# DELPHI.net
KiCad netlist of a schematic drawn in Altium Designer
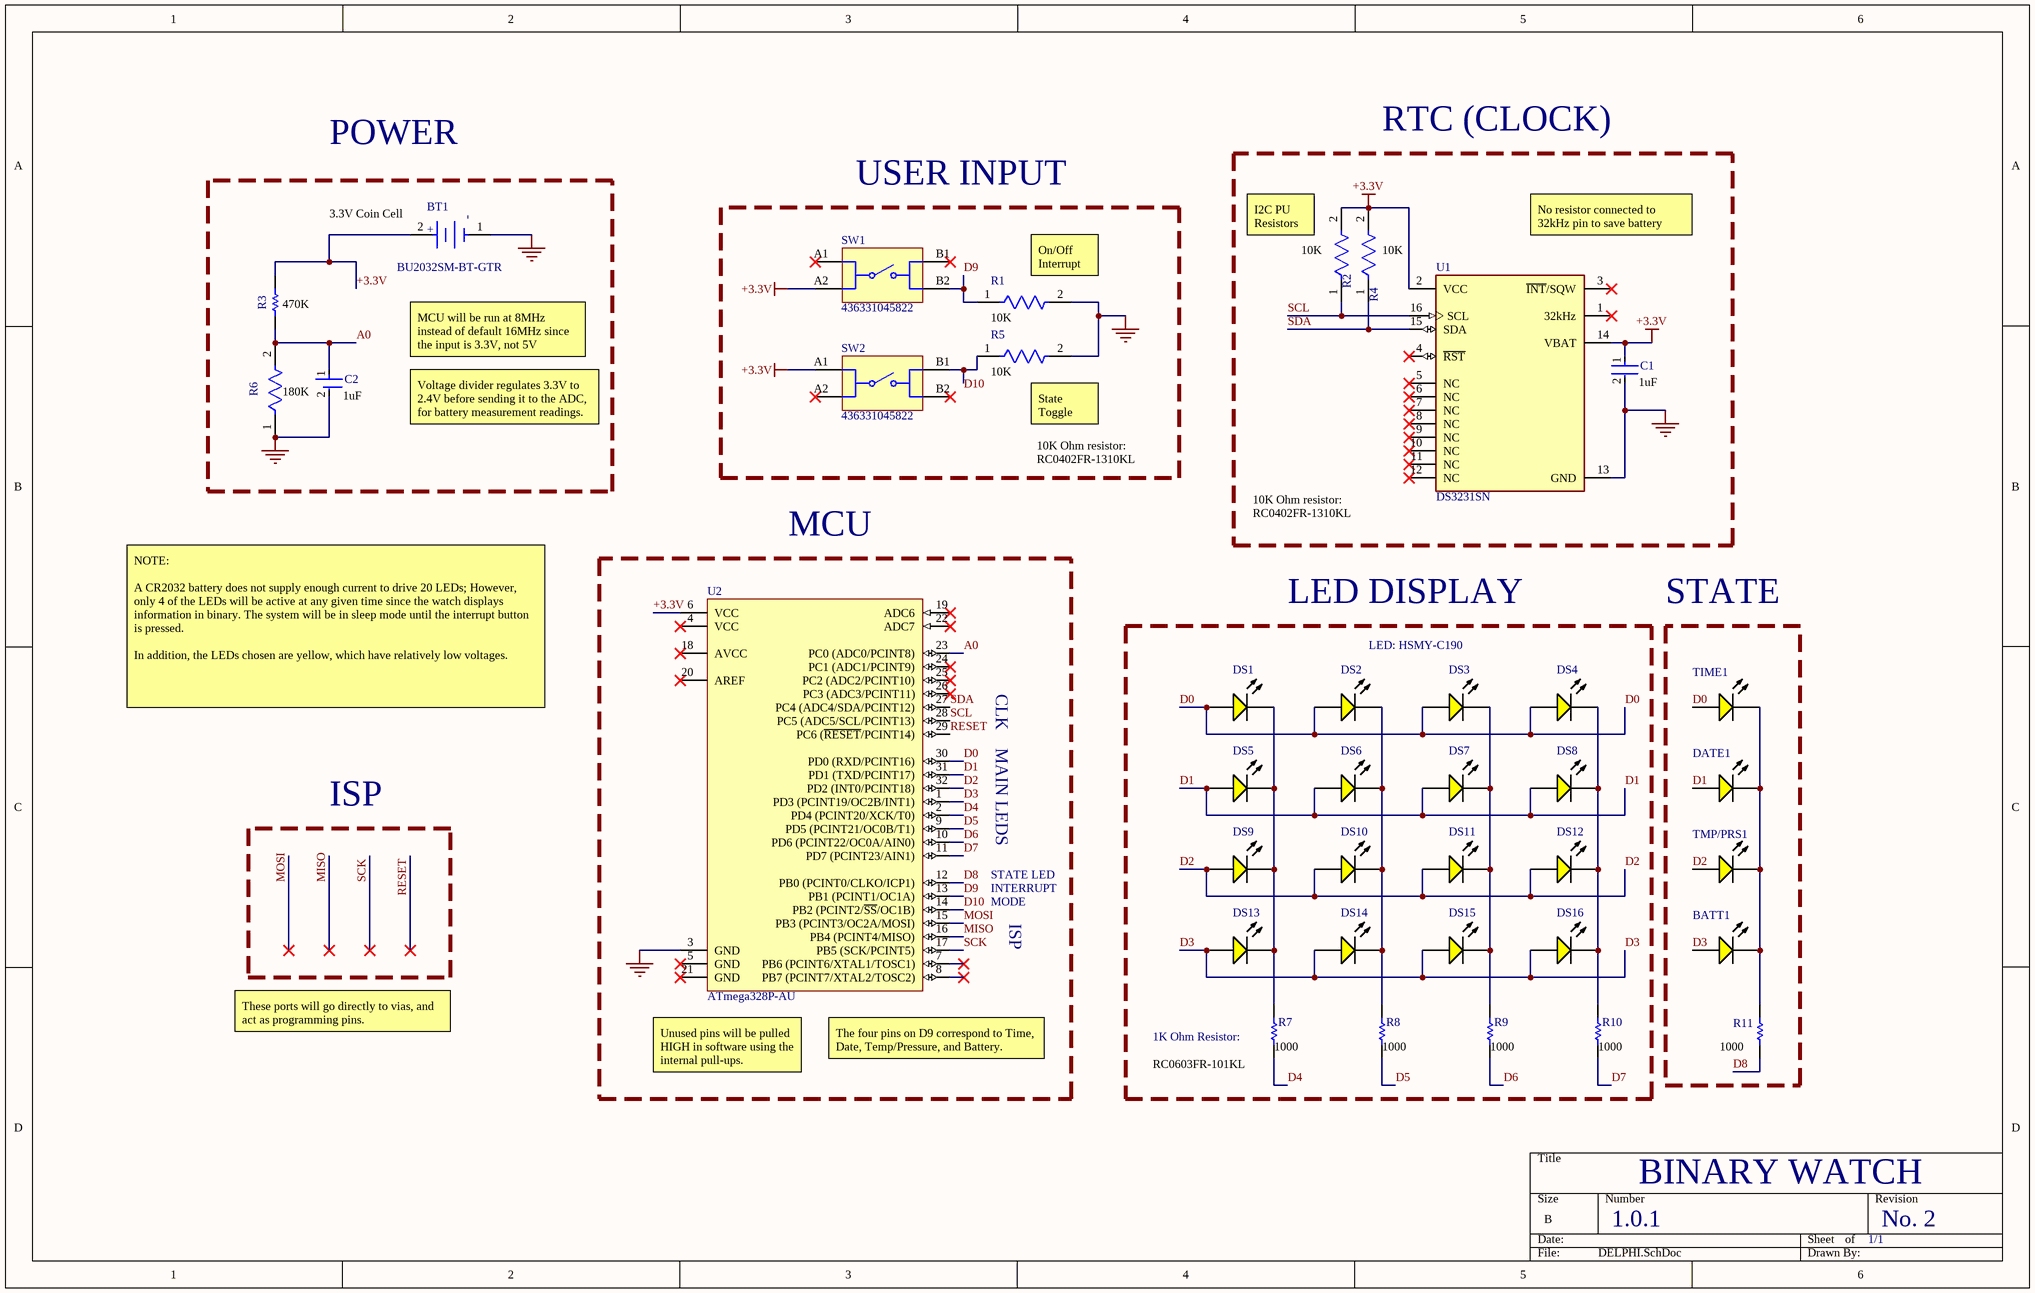
[diagram p0: DELPHI.SchDoc]

(export (version "E")
  (design (tool "Eeschema 10.0.6"))
  (components
    (comp (ref "BATT1")
      (value "HSMY-C190")
      (footprint "AVAG-HSMX-C190_V")
      (description "LED Uni-Color Yellow, 65 mW, 20 mA, -40 to 85 degC, 2-Pin SMD, RoHS, Tape and Reel")
      (fields (field (name "TOLERANCE") "1%"))
      (libsource (lib "Altium Content Vault") (part "LED-YELLOW-AK-2"))
    )
    (comp (ref "BT1")
      (value "BU2032SM-BT-GTR")
      (footprint "FP-BU2032SM-BT-GTR-MFG")
      (description "BATTERY HOLDER COIN 20MM SMD")
      (libsource (lib "Altium Content Vault") (part "60d3b5b901a8747834971d0eb8cf3fd"))
    )
    (comp (ref "C1")
      (value "GRM155R61H105KE05D")
      (footprint "FP-GRM155-0_1-MFG")
      (description "CERAMIC CAP, MLCC 1UF 50VDC X5R")
      (libsource (lib "Altium Content Vault") (part "b4654b650e69147ec39a6b967a45e02"))
    )
    (comp (ref "C2")
      (value "GRM155R61H105KE05D")
      (footprint "FP-GRM155-0_1-MFG")
      (description "CERAMIC CAP, MLCC 1UF 50VDC X5R")
      (libsource (lib "Altium Content Vault") (part "b4654b650e69147ec39a6b967a45e02"))
    )
    (comp (ref "DATE1")
      (value "HSMY-C190")
      (footprint "AVAG-HSMX-C190_V")
      (description "LED Uni-Color Yellow, 65 mW, 20 mA, -40 to 85 degC, 2-Pin SMD, RoHS, Tape and Reel")
      (fields (field (name "TOLERANCE") "1%"))
      (libsource (lib "Altium Content Vault") (part "LED-YELLOW-AK-2"))
    )
    (comp (ref "DS1")
      (value "HSMY-C190")
      (footprint "AVAG-HSMX-C190_V")
      (description "LED Uni-Color Yellow, 65 mW, 20 mA, -40 to 85 degC, 2-Pin SMD, RoHS, Tape and Reel")
      (fields (field (name "TOLERANCE") "1%"))
      (libsource (lib "Altium Content Vault") (part "LED-YELLOW-AK-2"))
    )
    (comp (ref "DS2")
      (value "HSMY-C190")
      (footprint "AVAG-HSMX-C190_V")
      (description "LED Uni-Color Yellow, 65 mW, 20 mA, -40 to 85 degC, 2-Pin SMD, RoHS, Tape and Reel")
      (fields (field (name "TOLERANCE") "1%"))
      (libsource (lib "Altium Content Vault") (part "LED-YELLOW-AK-2"))
    )
    (comp (ref "DS3")
      (value "HSMY-C190")
      (footprint "AVAG-HSMX-C190_V")
      (description "LED Uni-Color Yellow, 65 mW, 20 mA, -40 to 85 degC, 2-Pin SMD, RoHS, Tape and Reel")
      (fields (field (name "TOLERANCE") "1%"))
      (libsource (lib "Altium Content Vault") (part "LED-YELLOW-AK-2"))
    )
    (comp (ref "DS4")
      (value "HSMY-C190")
      (footprint "AVAG-HSMX-C190_V")
      (description "LED Uni-Color Yellow, 65 mW, 20 mA, -40 to 85 degC, 2-Pin SMD, RoHS, Tape and Reel")
      (fields (field (name "TOLERANCE") "1%"))
      (libsource (lib "Altium Content Vault") (part "LED-YELLOW-AK-2"))
    )
    (comp (ref "DS5")
      (value "HSMY-C190")
      (footprint "AVAG-HSMX-C190_V")
      (description "LED Uni-Color Yellow, 65 mW, 20 mA, -40 to 85 degC, 2-Pin SMD, RoHS, Tape and Reel")
      (fields (field (name "TOLERANCE") "1%"))
      (libsource (lib "Altium Content Vault") (part "LED-YELLOW-AK-2"))
    )
    (comp (ref "DS6")
      (value "HSMY-C190")
      (footprint "AVAG-HSMX-C190_V")
      (description "LED Uni-Color Yellow, 65 mW, 20 mA, -40 to 85 degC, 2-Pin SMD, RoHS, Tape and Reel")
      (fields (field (name "TOLERANCE") "1%"))
      (libsource (lib "Altium Content Vault") (part "LED-YELLOW-AK-2"))
    )
    (comp (ref "DS7")
      (value "HSMY-C190")
      (footprint "AVAG-HSMX-C190_V")
      (description "LED Uni-Color Yellow, 65 mW, 20 mA, -40 to 85 degC, 2-Pin SMD, RoHS, Tape and Reel")
      (fields (field (name "TOLERANCE") "1%"))
      (libsource (lib "Altium Content Vault") (part "LED-YELLOW-AK-2"))
    )
    (comp (ref "DS8")
      (value "HSMY-C190")
      (footprint "AVAG-HSMX-C190_V")
      (description "LED Uni-Color Yellow, 65 mW, 20 mA, -40 to 85 degC, 2-Pin SMD, RoHS, Tape and Reel")
      (fields (field (name "TOLERANCE") "1%"))
      (libsource (lib "Altium Content Vault") (part "LED-YELLOW-AK-2"))
    )
    (comp (ref "DS9")
      (value "HSMY-C190")
      (footprint "AVAG-HSMX-C190_V")
      (description "LED Uni-Color Yellow, 65 mW, 20 mA, -40 to 85 degC, 2-Pin SMD, RoHS, Tape and Reel")
      (fields (field (name "TOLERANCE") "1%"))
      (libsource (lib "Altium Content Vault") (part "LED-YELLOW-AK-2"))
    )
    (comp (ref "DS10")
      (value "HSMY-C190")
      (footprint "AVAG-HSMX-C190_V")
      (description "LED Uni-Color Yellow, 65 mW, 20 mA, -40 to 85 degC, 2-Pin SMD, RoHS, Tape and Reel")
      (fields (field (name "TOLERANCE") "1%"))
      (libsource (lib "Altium Content Vault") (part "LED-YELLOW-AK-2"))
    )
    (comp (ref "DS11")
      (value "HSMY-C190")
      (footprint "AVAG-HSMX-C190_V")
      (description "LED Uni-Color Yellow, 65 mW, 20 mA, -40 to 85 degC, 2-Pin SMD, RoHS, Tape and Reel")
      (fields (field (name "TOLERANCE") "1%"))
      (libsource (lib "Altium Content Vault") (part "LED-YELLOW-AK-2"))
    )
    (comp (ref "DS12")
      (value "HSMY-C190")
      (footprint "AVAG-HSMX-C190_V")
      (description "LED Uni-Color Yellow, 65 mW, 20 mA, -40 to 85 degC, 2-Pin SMD, RoHS, Tape and Reel")
      (fields (field (name "TOLERANCE") "1%"))
      (libsource (lib "Altium Content Vault") (part "LED-YELLOW-AK-2"))
    )
    (comp (ref "DS13")
      (value "HSMY-C190")
      (footprint "AVAG-HSMX-C190_V")
      (description "LED Uni-Color Yellow, 65 mW, 20 mA, -40 to 85 degC, 2-Pin SMD, RoHS, Tape and Reel")
      (fields (field (name "TOLERANCE") "1%"))
      (libsource (lib "Altium Content Vault") (part "LED-YELLOW-AK-2"))
    )
    (comp (ref "DS14")
      (value "HSMY-C190")
      (footprint "AVAG-HSMX-C190_V")
      (description "LED Uni-Color Yellow, 65 mW, 20 mA, -40 to 85 degC, 2-Pin SMD, RoHS, Tape and Reel")
      (fields (field (name "TOLERANCE") "1%"))
      (libsource (lib "Altium Content Vault") (part "LED-YELLOW-AK-2"))
    )
    (comp (ref "DS15")
      (value "HSMY-C190")
      (footprint "AVAG-HSMX-C190_V")
      (description "LED Uni-Color Yellow, 65 mW, 20 mA, -40 to 85 degC, 2-Pin SMD, RoHS, Tape and Reel")
      (fields (field (name "TOLERANCE") "1%"))
      (libsource (lib "Altium Content Vault") (part "LED-YELLOW-AK-2"))
    )
    (comp (ref "DS16")
      (value "HSMY-C190")
      (footprint "AVAG-HSMX-C190_V")
      (description "LED Uni-Color Yellow, 65 mW, 20 mA, -40 to 85 degC, 2-Pin SMD, RoHS, Tape and Reel")
      (fields (field (name "TOLERANCE") "1%"))
      (libsource (lib "Altium Content Vault") (part "LED-YELLOW-AK-2"))
    )
    (comp (ref "R1")
      (value "RC0402FR-1310KL")
      (footprint "FP-RC0402-0_4-IPC_A")
      (description "RESISTOR 0402 10K 1%")
      (fields (field (name "TOLERANCE") "1%"))
      (libsource (lib "Altium Content Vault") (part "1029c3af85768c4190bb7ad29bc67b5"))
    )
    (comp (ref "R2")
      (value "RC0402FR-1310KL")
      (footprint "FP-RC0402-0_4-IPC_A")
      (description "RESISTOR 0402 10K 1%")
      (fields (field (name "TOLERANCE") "1%"))
      (libsource (lib "Altium Content Vault") (part "1029c3af85768c4190bb7ad29bc67b5"))
    )
    (comp (ref "R3")
      (value "~")
      (footprint "RESC1005X40X25NL05T10")
      (fields (field (name "PART NUMBER") "RC0402FR-07470KL") (field (name "MANUFACTURER") "Yageo / Phycomp"))
      (libsource (lib "Altium Content Vault") (part "RES"))
    )
    (comp (ref "R4")
      (value "RC0402FR-1310KL")
      (footprint "FP-RC0402-0_4-IPC_A")
      (description "RESISTOR 0402 10K 1%")
      (fields (field (name "TOLERANCE") "1%"))
      (libsource (lib "Altium Content Vault") (part "1029c3af85768c4190bb7ad29bc67b5"))
    )
    (comp (ref "R5")
      (value "RC0402FR-1310KL")
      (footprint "FP-RC0402-0_4-IPC_A")
      (description "RESISTOR 0402 10K 1%")
      (fields (field (name "TOLERANCE") "1%"))
      (libsource (lib "Altium Content Vault") (part "1029c3af85768c4190bb7ad29bc67b5"))
    )
    (comp (ref "R6")
      (value "~")
      (footprint "FP-CR0402-IPC_A")
      (description "Thick Film Chip Resistors 0402 180kΩ 0.0625W 1% 100ppm/°C")
      (fields (field (name "TOLERANCE") "1%"))
      (libsource (lib "Altium Content Vault") (part "1029c3af85768c4190bb7ad29bc67b5"))
    )
    (comp (ref "R7")
      (value "RC0603FR-101KL")
      (footprint "RESC1608X55X25LL10T15")
      (fields (field (name "MANUFACTURER") "Yageo"))
      (libsource (lib "Altium Content Vault") (part "RES"))
    )
    (comp (ref "R8")
      (value "RC0603FR-101KL")
      (footprint "RESC1608X55X25LL10T15")
      (fields (field (name "MANUFACTURER") "Yageo"))
      (libsource (lib "Altium Content Vault") (part "RES"))
    )
    (comp (ref "R9")
      (value "RC0603FR-101KL")
      (footprint "RESC1608X55X25LL10T15")
      (fields (field (name "MANUFACTURER") "Yageo"))
      (libsource (lib "Altium Content Vault") (part "RES"))
    )
    (comp (ref "R10")
      (value "RC0603FR-101KL")
      (footprint "RESC1608X55X25LL10T15")
      (fields (field (name "MANUFACTURER") "Yageo"))
      (libsource (lib "Altium Content Vault") (part "RES"))
    )
    (comp (ref "R11")
      (value "RC0603FR-101KL")
      (footprint "RESC1608X55X25LL10T15")
      (fields (field (name "MANUFACTURER") "Yageo"))
      (libsource (lib "Altium Content Vault") (part "RES"))
    )
    (comp (ref "SW1")
      (value "436331045822")
      (footprint "436331045822")
      (libsource (lib "Altium Content Vault") (part "SPST-NO_4P"))
    )
    (comp (ref "SW2")
      (value "436331045822")
      (footprint "436331045822")
      (libsource (lib "Altium Content Vault") (part "SPST-NO_4P"))
    )
    (comp (ref "TIME1")
      (value "HSMY-C190")
      (footprint "AVAG-HSMX-C190_V")
      (description "LED Uni-Color Yellow, 65 mW, 20 mA, -40 to 85 degC, 2-Pin SMD, RoHS, Tape and Reel")
      (fields (field (name "TOLERANCE") "1%"))
      (libsource (lib "Altium Content Vault") (part "LED-YELLOW-AK-2"))
    )
    (comp (ref "TMP/PRS1")
      (value "HSMY-C190")
      (footprint "AVAG-HSMX-C190_V")
      (description "LED Uni-Color Yellow, 65 mW, 20 mA, -40 to 85 degC, 2-Pin SMD, RoHS, Tape and Reel")
      (fields (field (name "TOLERANCE") "1%"))
      (libsource (lib "Altium Content Vault") (part "LED-YELLOW-AK-2"))
    )
    (comp (ref "U1")
      (value "DS3231SN")
      (footprint "FP-W16-H2-MFG")
      (description "IC RTC CLK/CALENDAR I2C 16-SOIC")
      (libsource (lib "Altium Content Vault") (part "49e129a02c1e013a88f81c98964c20e"))
    )
    (comp (ref "U2")
      (value "ATmega328P-AU")
      (footprint "32A_M")
      (libsource (lib "Altium Content Vault") (part "MC-8B-ATM48-SQ32"))
    )
  )
  (nets
    (net (code "1") (name "+3.3V") (class "Default")
      (node (ref "BT1") (pin "2") (pinfunction "A_2") (pintype "passive"))
      (node (ref "C1") (pin "1") (pinfunction "1_1") (pintype "passive"))
      (node (ref "R2") (pin "2") (pinfunction "2_2") (pintype "passive"))
      (node (ref "R3") (pin "1") (pinfunction "1_1") (pintype "passive"))
      (node (ref "R4") (pin "2") (pinfunction "2_2") (pintype "passive"))
      (node (ref "SW1") (pin "A2") (pinfunction "A2_A2") (pintype "passive"))
      (node (ref "SW2") (pin "A1") (pinfunction "A1_A1") (pintype "passive"))
      (node (ref "U1") (pin "14") (pinfunction "VBAT_14") (pintype "power_in"))
      (node (ref "U1") (pin "2") (pinfunction "VCC_2") (pintype "power_in"))
      (node (ref "U2") (pin "6") (pinfunction "VCC_6") (pintype "power_in"))
    )
    (net (code "2") (name "/A0") (class "Default")
      (node (ref "C2") (pin "1") (pinfunction "1_1") (pintype "passive"))
      (node (ref "R3") (pin "2") (pinfunction "2_2") (pintype "passive"))
      (node (ref "R6") (pin "2") (pinfunction "2_2") (pintype "passive"))
      (node (ref "U2") (pin "23") (pinfunction "PC0_(ADC0/PCINT8)_23") (pintype "bidirectional"))
    )
    (net (code "3") (name "/D0") (class "Default")
      (node (ref "DS1") (pin "1") (pinfunction "A_1") (pintype "passive"))
      (node (ref "DS2") (pin "1") (pinfunction "A_1") (pintype "passive"))
      (node (ref "DS3") (pin "1") (pinfunction "A_1") (pintype "passive"))
      (node (ref "DS4") (pin "1") (pinfunction "A_1") (pintype "passive"))
      (node (ref "TIME1") (pin "1") (pinfunction "A_1") (pintype "passive"))
      (node (ref "U2") (pin "30") (pinfunction "PD0_(RXD/PCINT16)_30") (pintype "bidirectional"))
    )
    (net (code "4") (name "/D1") (class "Default")
      (node (ref "DATE1") (pin "1") (pinfunction "A_1") (pintype "passive"))
      (node (ref "DS5") (pin "1") (pinfunction "A_1") (pintype "passive"))
      (node (ref "DS6") (pin "1") (pinfunction "A_1") (pintype "passive"))
      (node (ref "DS7") (pin "1") (pinfunction "A_1") (pintype "passive"))
      (node (ref "DS8") (pin "1") (pinfunction "A_1") (pintype "passive"))
      (node (ref "U2") (pin "31") (pinfunction "PD1_(TXD/PCINT17)_31") (pintype "bidirectional"))
    )
    (net (code "5") (name "/D2") (class "Default")
      (node (ref "DS10") (pin "1") (pinfunction "A_1") (pintype "passive"))
      (node (ref "DS11") (pin "1") (pinfunction "A_1") (pintype "passive"))
      (node (ref "DS12") (pin "1") (pinfunction "A_1") (pintype "passive"))
      (node (ref "DS9") (pin "1") (pinfunction "A_1") (pintype "passive"))
      (node (ref "TMP/PRS1") (pin "1") (pinfunction "A_1") (pintype "passive"))
      (node (ref "U2") (pin "32") (pinfunction "PD2_(INT0/PCINT18)_32") (pintype "bidirectional"))
    )
    (net (code "6") (name "/D3") (class "Default")
      (node (ref "BATT1") (pin "1") (pinfunction "A_1") (pintype "passive"))
      (node (ref "DS13") (pin "1") (pinfunction "A_1") (pintype "passive"))
      (node (ref "DS14") (pin "1") (pinfunction "A_1") (pintype "passive"))
      (node (ref "DS15") (pin "1") (pinfunction "A_1") (pintype "passive"))
      (node (ref "DS16") (pin "1") (pinfunction "A_1") (pintype "passive"))
      (node (ref "U2") (pin "1") (pinfunction "PD3_(PCINT19/OC2B/INT1)_1") (pintype "bidirectional"))
    )
    (net (code "7") (name "/D4") (class "Default")
      (node (ref "R7") (pin "1") (pinfunction "1_1") (pintype "passive"))
      (node (ref "U2") (pin "2") (pinfunction "PD4_(PCINT20/XCK/T0)_2") (pintype "bidirectional"))
    )
    (net (code "8") (name "/D5") (class "Default")
      (node (ref "R8") (pin "1") (pinfunction "1_1") (pintype "passive"))
      (node (ref "U2") (pin "9") (pinfunction "PD5_(PCINT21/OC0B/T1)_9") (pintype "bidirectional"))
    )
    (net (code "9") (name "/D6") (class "Default")
      (node (ref "R9") (pin "1") (pinfunction "1_1") (pintype "passive"))
      (node (ref "U2") (pin "10") (pinfunction "PD6_(PCINT22/OC0A/AIN0)_10") (pintype "bidirectional"))
    )
    (net (code "10") (name "/D7") (class "Default")
      (node (ref "R10") (pin "1") (pinfunction "1_1") (pintype "passive"))
      (node (ref "U2") (pin "11") (pinfunction "PD7_(PCINT23/AIN1)_11") (pintype "bidirectional"))
    )
    (net (code "11") (name "/D8") (class "Default")
      (node (ref "R11") (pin "1") (pinfunction "1_1") (pintype "passive"))
      (node (ref "U2") (pin "12") (pinfunction "PB0_(PCINT0/CLKO/ICP1)_12") (pintype "bidirectional"))
    )
    (net (code "12") (name "/D9") (class "Default")
      (node (ref "R1") (pin "1") (pinfunction "1_1") (pintype "passive"))
      (node (ref "SW1") (pin "B2") (pinfunction "B2_B2") (pintype "passive"))
      (node (ref "U2") (pin "13") (pinfunction "PB1_(PCINT1/OC1A)_13") (pintype "bidirectional"))
    )
    (net (code "13") (name "/D10") (class "Default")
      (node (ref "R5") (pin "1") (pinfunction "1_1") (pintype "passive"))
      (node (ref "SW2") (pin "B1") (pinfunction "B1_B1") (pintype "passive"))
      (node (ref "U2") (pin "14") (pinfunction "PB2_(PCINT2/~{SS}/OC1B)_14") (pintype "bidirectional"))
    )
    (net (code "14") (name "/MISO") (class "Default")
      (node (ref "U2") (pin "16") (pinfunction "PB4_(PCINT4/MISO)_16") (pintype "bidirectional"))
    )
    (net (code "15") (name "/MOSI") (class "Default")
      (node (ref "U2") (pin "15") (pinfunction "PB3_(PCINT3/OC2A/MOSI)_15") (pintype "bidirectional"))
    )
    (net (code "16") (name "/RESET") (class "Default")
      (node (ref "U2") (pin "29") (pinfunction "PC6_(~{RESET}/PCINT14)_29") (pintype "bidirectional+no_connect"))
    )
    (net (code "17") (name "/SCK") (class "Default")
      (node (ref "U2") (pin "17") (pinfunction "PB5_(SCK/PCINT5)_17") (pintype "bidirectional"))
    )
    (net (code "18") (name "/SCL") (class "Default")
      (node (ref "R2") (pin "1") (pinfunction "1_1") (pintype "passive"))
      (node (ref "U1") (pin "16") (pinfunction "SCL_16") (pintype "input"))
      (node (ref "U2") (pin "28") (pinfunction "PC5_(ADC5/SCL/PCINT13)_28") (pintype "bidirectional"))
    )
    (net (code "19") (name "/SDA") (class "Default")
      (node (ref "R4") (pin "1") (pinfunction "1_1") (pintype "passive"))
      (node (ref "U1") (pin "15") (pinfunction "SDA_15") (pintype "bidirectional"))
      (node (ref "U2") (pin "27") (pinfunction "PC4_(ADC4/SDA/PCINT12)_27") (pintype "bidirectional"))
    )
    (net (code "20") (name "<NO NET>") (class "Default")
      (node (ref "BT1") (pin "1") (pinfunction "C_1") (pintype "passive"))
      (node (ref "C1") (pin "2") (pinfunction "2_2") (pintype "passive"))
      (node (ref "C2") (pin "2") (pinfunction "2_2") (pintype "passive"))
      (node (ref "R1") (pin "2") (pinfunction "2_2") (pintype "passive"))
      (node (ref "R5") (pin "2") (pinfunction "2_2") (pintype "passive"))
      (node (ref "R6") (pin "1") (pinfunction "1_1") (pintype "passive"))
      (node (ref "U1") (pin "13") (pinfunction "GND_13") (pintype "power_in"))
      (node (ref "U2") (pin "3") (pinfunction "GND_3") (pintype "power_in"))
    )
    (net (code "21") (name "Net-(BATT1-K)") (class "Default")
      (node (ref "BATT1") (pin "2") (pinfunction "K_2") (pintype "passive"))
      (node (ref "DATE1") (pin "2") (pinfunction "K_2") (pintype "passive"))
      (node (ref "R11") (pin "2") (pinfunction "2_2") (pintype "passive"))
      (node (ref "TIME1") (pin "2") (pinfunction "K_2") (pintype "passive"))
      (node (ref "TMP/PRS1") (pin "2") (pinfunction "K_2") (pintype "passive"))
    )
    (net (code "22") (name "Net-(DS1-K)") (class "Default")
      (node (ref "DS1") (pin "2") (pinfunction "K_2") (pintype "passive"))
      (node (ref "DS13") (pin "2") (pinfunction "K_2") (pintype "passive"))
      (node (ref "DS5") (pin "2") (pinfunction "K_2") (pintype "passive"))
      (node (ref "DS9") (pin "2") (pinfunction "K_2") (pintype "passive"))
      (node (ref "R7") (pin "2") (pinfunction "2_2") (pintype "passive"))
    )
    (net (code "23") (name "Net-(DS10-K)") (class "Default")
      (node (ref "DS10") (pin "2") (pinfunction "K_2") (pintype "passive"))
      (node (ref "DS14") (pin "2") (pinfunction "K_2") (pintype "passive"))
      (node (ref "DS2") (pin "2") (pinfunction "K_2") (pintype "passive"))
      (node (ref "DS6") (pin "2") (pinfunction "K_2") (pintype "passive"))
      (node (ref "R8") (pin "2") (pinfunction "2_2") (pintype "passive"))
    )
    (net (code "24") (name "Net-(DS11-K)") (class "Default")
      (node (ref "DS11") (pin "2") (pinfunction "K_2") (pintype "passive"))
      (node (ref "DS15") (pin "2") (pinfunction "K_2") (pintype "passive"))
      (node (ref "DS3") (pin "2") (pinfunction "K_2") (pintype "passive"))
      (node (ref "DS7") (pin "2") (pinfunction "K_2") (pintype "passive"))
      (node (ref "R9") (pin "2") (pinfunction "2_2") (pintype "passive"))
    )
    (net (code "25") (name "Net-(DS12-K)") (class "Default")
      (node (ref "DS12") (pin "2") (pinfunction "K_2") (pintype "passive"))
      (node (ref "DS16") (pin "2") (pinfunction "K_2") (pintype "passive"))
      (node (ref "DS4") (pin "2") (pinfunction "K_2") (pintype "passive"))
      (node (ref "DS8") (pin "2") (pinfunction "K_2") (pintype "passive"))
      (node (ref "R10") (pin "2") (pinfunction "2_2") (pintype "passive"))
    )
    (net (code "26") (name "unconnected-(SW1-PadA1)") (class "Default")
      (node (ref "SW1") (pin "A1") (pinfunction "A1_A1") (pintype "passive+no_connect"))
    )
    (net (code "27") (name "unconnected-(SW1-PadB1)") (class "Default")
      (node (ref "SW1") (pin "B1") (pinfunction "B1_B1") (pintype "passive+no_connect"))
    )
    (net (code "28") (name "unconnected-(SW2-PadA2)") (class "Default")
      (node (ref "SW2") (pin "A2") (pinfunction "A2_A2") (pintype "passive+no_connect"))
    )
    (net (code "29") (name "unconnected-(SW2-PadB2)") (class "Default")
      (node (ref "SW2") (pin "B2") (pinfunction "B2_B2") (pintype "passive+no_connect"))
    )
    (net (code "30") (name "unconnected-(U1-32kHz-Pad1)") (class "Default")
      (node (ref "U1") (pin "1") (pinfunction "32kHz_1") (pintype "open_collector+no_connect"))
    )
    (net (code "31") (name "unconnected-(U1-NC-Pad5)") (class "Default")
      (node (ref "U1") (pin "5") (pinfunction "NC_5") (pintype "passive+no_connect"))
    )
    (net (code "32") (name "unconnected-(U1-NC-Pad6)") (class "Default")
      (node (ref "U1") (pin "6") (pinfunction "NC_6") (pintype "passive+no_connect"))
    )
    (net (code "33") (name "unconnected-(U1-NC-Pad7)") (class "Default")
      (node (ref "U1") (pin "7") (pinfunction "NC_7") (pintype "passive+no_connect"))
    )
    (net (code "34") (name "unconnected-(U1-NC-Pad8)") (class "Default")
      (node (ref "U1") (pin "8") (pinfunction "NC_8") (pintype "passive+no_connect"))
    )
    (net (code "35") (name "unconnected-(U1-NC-Pad9)") (class "Default")
      (node (ref "U1") (pin "9") (pinfunction "NC_9") (pintype "passive+no_connect"))
    )
    (net (code "36") (name "unconnected-(U1-NC-Pad10)") (class "Default")
      (node (ref "U1") (pin "10") (pinfunction "NC_10") (pintype "passive+no_connect"))
    )
    (net (code "37") (name "unconnected-(U1-NC-Pad11)") (class "Default")
      (node (ref "U1") (pin "11") (pinfunction "NC_11") (pintype "passive+no_connect"))
    )
    (net (code "38") (name "unconnected-(U1-NC-Pad12)") (class "Default")
      (node (ref "U1") (pin "12") (pinfunction "NC_12") (pintype "passive+no_connect"))
    )
    (net (code "39") (name "unconnected-(U1-~{INT}{slash}SQW-Pad3)") (class "Default")
      (node (ref "U1") (pin "3") (pinfunction "~{INT}/SQW_3") (pintype "open_collector+no_connect"))
    )
    (net (code "40") (name "unconnected-(U1-~{RST}-Pad4)") (class "Default")
      (node (ref "U1") (pin "4") (pinfunction "~{RST}_4") (pintype "bidirectional+no_connect"))
    )
    (net (code "41") (name "unconnected-(U2-ADC6-Pad19)") (class "Default")
      (node (ref "U2") (pin "19") (pinfunction "ADC6_19") (pintype "input+no_connect"))
    )
    (net (code "42") (name "unconnected-(U2-ADC7-Pad22)") (class "Default")
      (node (ref "U2") (pin "22") (pinfunction "ADC7_22") (pintype "input+no_connect"))
    )
    (net (code "43") (name "unconnected-(U2-AREF-Pad20)") (class "Default")
      (node (ref "U2") (pin "20") (pinfunction "AREF_20") (pintype "passive+no_connect"))
    )
    (net (code "44") (name "unconnected-(U2-AVCC-Pad18)") (class "Default")
      (node (ref "U2") (pin "18") (pinfunction "AVCC_18") (pintype "power_in+no_connect"))
    )
    (net (code "45") (name "unconnected-(U2-GND-Pad5)") (class "Default")
      (node (ref "U2") (pin "5") (pinfunction "GND_5") (pintype "power_in+no_connect"))
    )
    (net (code "46") (name "unconnected-(U2-GND-Pad21)") (class "Default")
      (node (ref "U2") (pin "21") (pinfunction "GND_21") (pintype "power_in+no_connect"))
    )
    (net (code "47") (name "unconnected-(U2-PB6_(PCINT6{slash}XTAL1{slash}TOSC1)-Pad7)") (class "Default")
      (node (ref "U2") (pin "7") (pinfunction "PB6_(PCINT6/XTAL1/TOSC1)_7") (pintype "bidirectional+no_connect"))
    )
    (net (code "48") (name "unconnected-(U2-PB7_(PCINT7{slash}XTAL2{slash}TOSC2)-Pad8)") (class "Default")
      (node (ref "U2") (pin "8") (pinfunction "PB7_(PCINT7/XTAL2/TOSC2)_8") (pintype "bidirectional+no_connect"))
    )
    (net (code "49") (name "unconnected-(U2-PC1_(ADC1{slash}PCINT9)-Pad24)") (class "Default")
      (node (ref "U2") (pin "24") (pinfunction "PC1_(ADC1/PCINT9)_24") (pintype "bidirectional+no_connect"))
    )
    (net (code "50") (name "unconnected-(U2-PC2_(ADC2{slash}PCINT10)-Pad25)") (class "Default")
      (node (ref "U2") (pin "25") (pinfunction "PC2_(ADC2/PCINT10)_25") (pintype "bidirectional+no_connect"))
    )
    (net (code "51") (name "unconnected-(U2-PC3_(ADC3{slash}PCINT11)-Pad26)") (class "Default")
      (node (ref "U2") (pin "26") (pinfunction "PC3_(ADC3/PCINT11)_26") (pintype "bidirectional+no_connect"))
    )
    (net (code "52") (name "unconnected-(U2-VCC-Pad4)") (class "Default")
      (node (ref "U2") (pin "4") (pinfunction "VCC_4") (pintype "power_in+no_connect"))
    )
  )
)
